# uNav44_r1_1.net
KiCad netlist of a schematic drawn in EAGLE
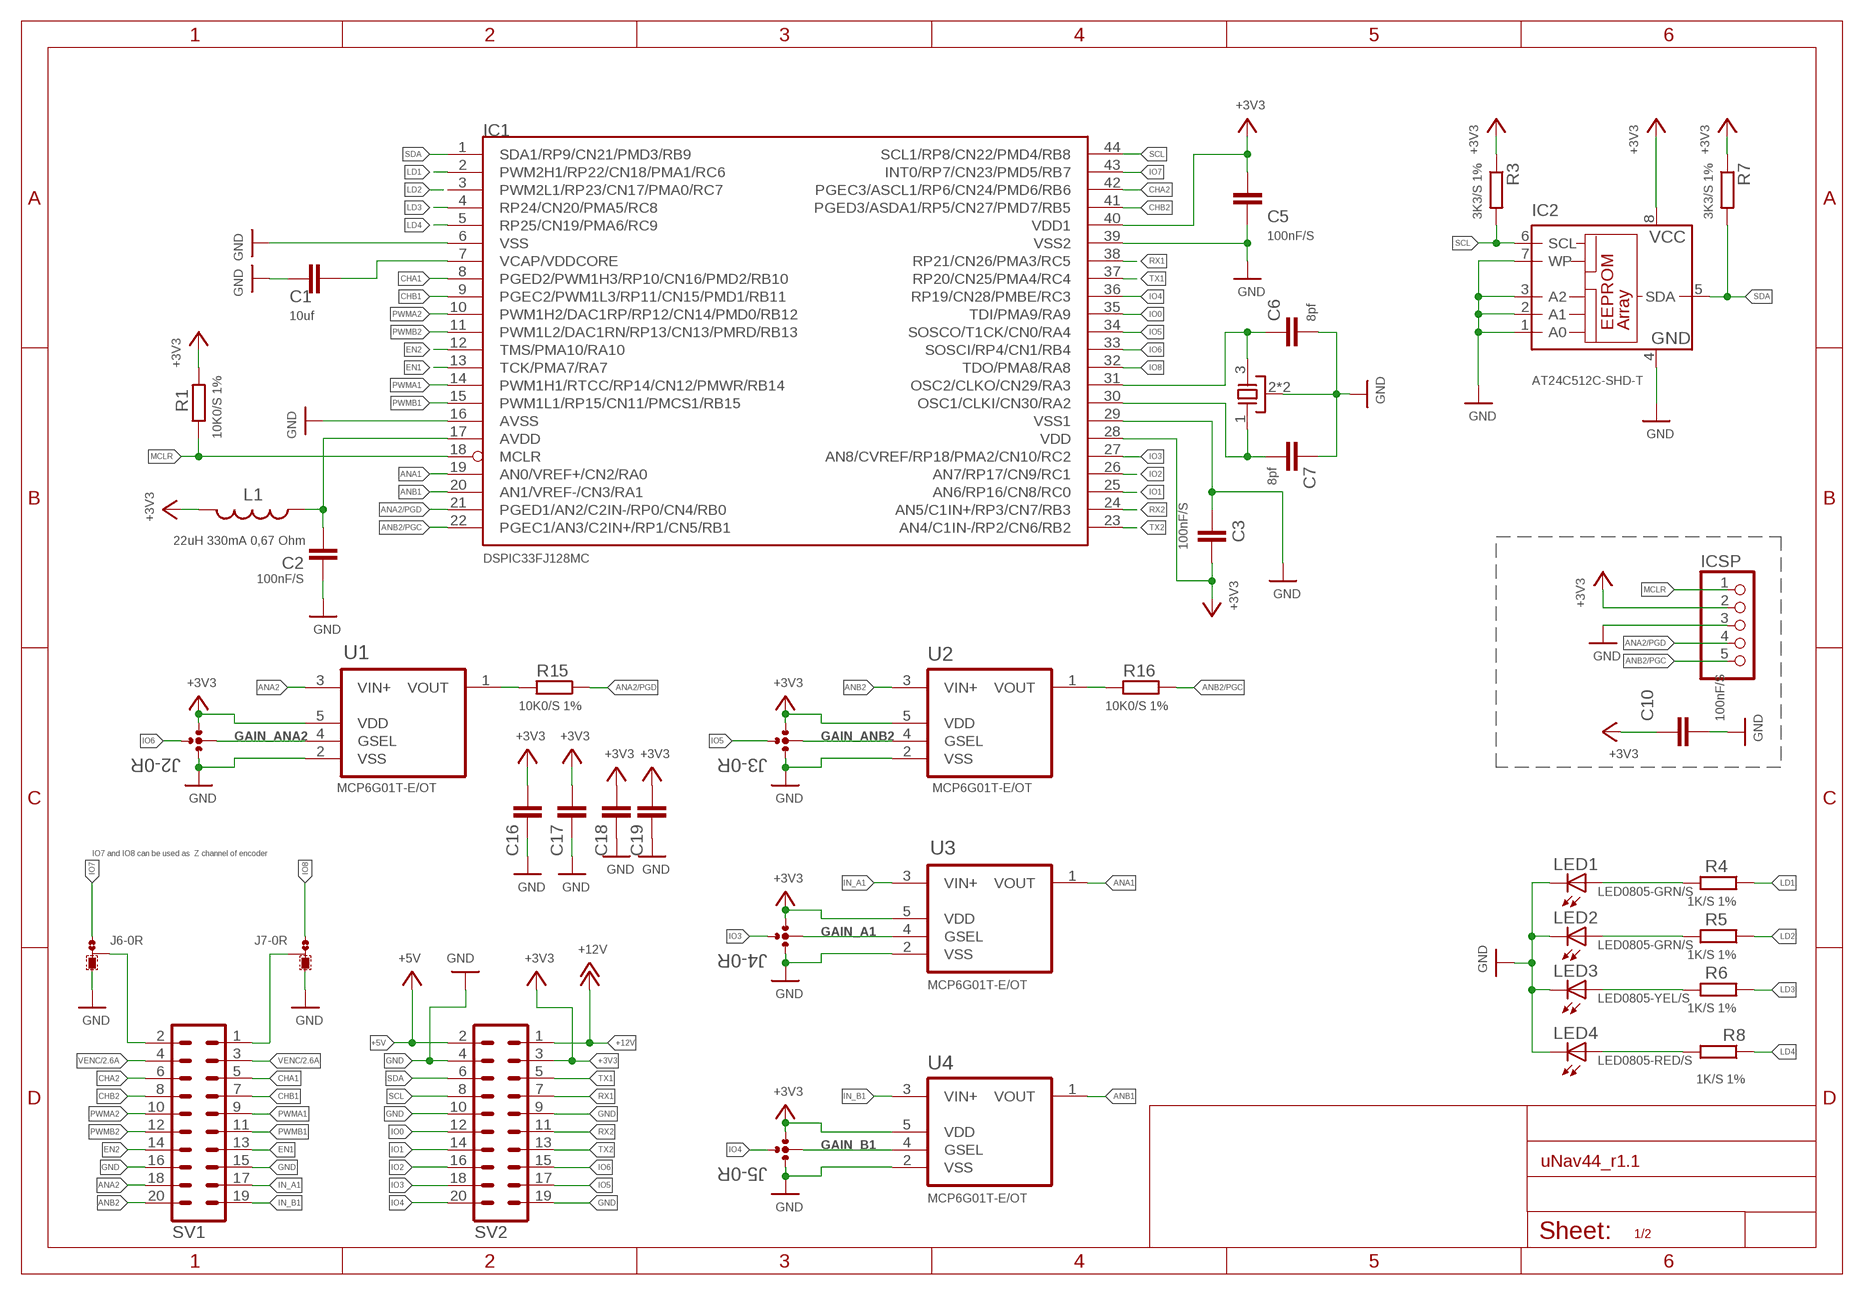
[diagram p0: schematic, sheet 1]
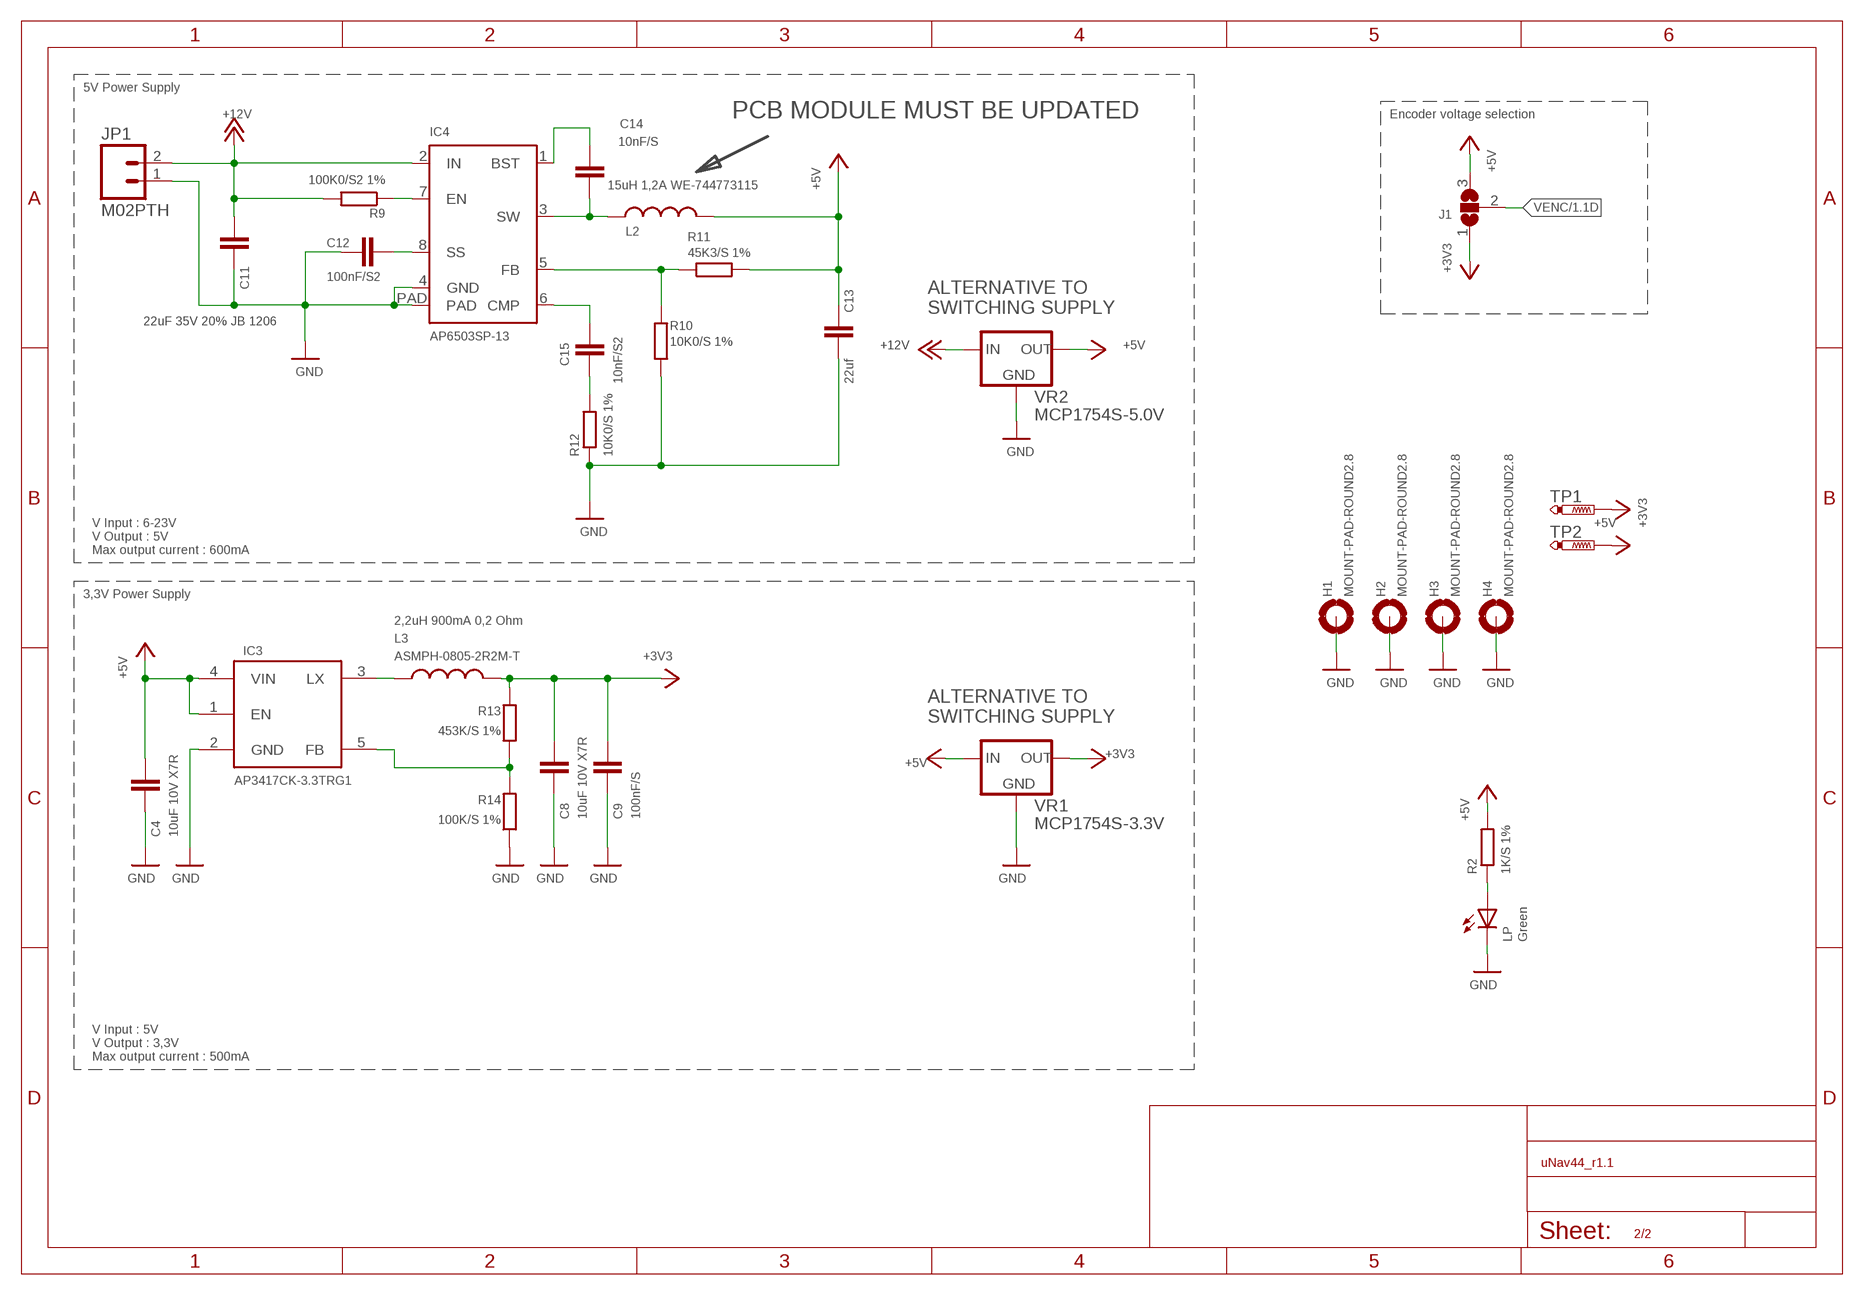
[diagram p1: schematic, sheet 2]

(export (version "E")
  (design (tool "Eeschema 10.0.6"))
  (components
    (comp (ref "C4")
      (value "10uF 10V X7R")
      (footprint "eagle-import:C0805")
      (libsource (lib "eagle-import") (part "C-EUC0805"))
    )
    (comp (ref "C8")
      (value "10uF 10V X7R")
      (footprint "eagle-import:C0805")
      (libsource (lib "eagle-import") (part "C-EUC0805"))
    )
    (comp (ref "C9")
      (value "100nF/S")
      (footprint "eagle-import:C0603")
      (libsource (lib "eagle-import") (part "C-EUC0603"))
    )
    (comp (ref "C11")
      (value "22uF 35V 20% JB 1206")
      (footprint "eagle-import:C1206")
      (libsource (lib "eagle-import") (part "C-EUC1206"))
    )
    (comp (ref "C12")
      (value "100nF/S2")
      (footprint "eagle-import:C0603")
      (libsource (lib "eagle-import") (part "C-EUC0603"))
    )
    (comp (ref "C13")
      (value "22uf")
      (footprint "eagle-import:C1206")
      (libsource (lib "eagle-import") (part "C-EUC1206"))
    )
    (comp (ref "C14")
      (value "10nF/S")
      (footprint "eagle-import:C0603")
      (libsource (lib "eagle-import") (part "C-EUC0603"))
    )
    (comp (ref "C15")
      (value "10nF/S2")
      (footprint "eagle-import:C0603")
      (libsource (lib "eagle-import") (part "C-EUC0603"))
    )
    (comp (ref "H1")
      (value "MOUNT-PAD-ROUND2.8")
      (footprint "eagle-import:2,8-PAD")
      (libsource (lib "eagle-import") (part "MOUNT-PAD-ROUND2.8"))
    )
    (comp (ref "H2")
      (value "MOUNT-PAD-ROUND2.8")
      (footprint "eagle-import:2,8-PAD")
      (libsource (lib "eagle-import") (part "MOUNT-PAD-ROUND2.8"))
    )
    (comp (ref "H3")
      (value "MOUNT-PAD-ROUND2.8")
      (footprint "eagle-import:2,8-PAD")
      (libsource (lib "eagle-import") (part "MOUNT-PAD-ROUND2.8"))
    )
    (comp (ref "H4")
      (value "MOUNT-PAD-ROUND2.8")
      (footprint "eagle-import:2,8-PAD")
      (libsource (lib "eagle-import") (part "MOUNT-PAD-ROUND2.8"))
    )
    (comp (ref "IC3")
      (value "AP3417CK-3.3TRG1")
      (footprint "eagle-import:SOT-23-5")
      (libsource (lib "eagle-import") (part "AP3417CSOT-23-5"))
    )
    (comp (ref "IC4")
      (value "AP6503SP-13")
      (footprint "eagle-import:SO-8EP")
      (libsource (lib "eagle-import") (part "AP6503SP-13'SO-8EP'"))
    )
    (comp (ref "J1")
      (value "SJ2W")
      (footprint "eagle-import:SJ_2")
      (libsource (lib "eagle-import") (part "SJ2W"))
    )
    (comp (ref "JP1")
      (value "M02PTH")
      (footprint "eagle-import:1X02")
      (libsource (lib "eagle-import") (part "M02PTH"))
    )
    (comp (ref "L2")
      (value "15uH 1,2A WE-744773115")
      (footprint "eagle-import:1210")
      (libsource (lib "eagle-import") (part "INDUCTOR1210"))
    )
    (comp (ref "L3")
      (value "ASMPH-0805-2R2M-T")
      (footprint "eagle-import:0805")
      (libsource (lib "eagle-import") (part "INDUCTOR0805"))
    )
    (comp (ref "LP")
      (value "Green")
      (footprint "eagle-import:CHIPLED_0805")
      (libsource (lib "eagle-import") (part "LEDCHIPLED_0805"))
    )
    (comp (ref "R2")
      (value "1K/S 1%")
      (footprint "eagle-import:R0603")
      (libsource (lib "eagle-import") (part "R-EU_R0603"))
    )
    (comp (ref "R9")
      (value "100K0/S2 1%")
      (footprint "eagle-import:R0603")
      (libsource (lib "eagle-import") (part "R-EU_R0603"))
    )
    (comp (ref "R10")
      (value "10K0/S 1%")
      (footprint "eagle-import:R0603")
      (libsource (lib "eagle-import") (part "R-EU_R0603"))
    )
    (comp (ref "R11")
      (value "45K3/S 1%")
      (footprint "eagle-import:R0603")
      (libsource (lib "eagle-import") (part "R-EU_R0603"))
    )
    (comp (ref "R12")
      (value "10K0/S 1%")
      (footprint "eagle-import:R0603")
      (libsource (lib "eagle-import") (part "R-EU_R0603"))
    )
    (comp (ref "R13")
      (value "453K/S 1%")
      (footprint "eagle-import:R0603")
      (libsource (lib "eagle-import") (part "R-EU_R0603"))
    )
    (comp (ref "R14")
      (value "100K/S 1%")
      (footprint "eagle-import:R0603")
      (libsource (lib "eagle-import") (part "R-EU_R0603"))
    )
    (comp (ref "TP1")
      (value "PTR1TP07R")
      (footprint "eagle-import:TP07R")
      (libsource (lib "eagle-import") (part "PTR1TP07R"))
    )
    (comp (ref "TP2")
      (value "PTR1TP07R")
      (footprint "eagle-import:TP07R")
      (libsource (lib "eagle-import") (part "PTR1TP07R"))
    )
    (comp (ref "VR1")
      (value "MCP1754S-3.3V")
      (footprint "eagle-import:SOT89")
      (libsource (lib "eagle-import") (part "MCP1754S"))
    )
    (comp (ref "VR2")
      (value "MCP1754S-5.0V")
      (footprint "eagle-import:SOT89")
      (libsource (lib "eagle-import") (part "MCP1754S"))
    )
    (comp (ref "C1")
      (value "10uf")
      (footprint "eagle-import:C1206")
      (libsource (lib "eagle-import") (part "C-EUC1206"))
    )
    (comp (ref "C2")
      (value "100nF/S")
      (footprint "eagle-import:C0603")
      (libsource (lib "eagle-import") (part "C-EUC0603"))
    )
    (comp (ref "C3")
      (value "100nF/S")
      (footprint "eagle-import:C0603")
      (libsource (lib "eagle-import") (part "C-EUC0603"))
    )
    (comp (ref "C5")
      (value "100nF/S")
      (footprint "eagle-import:C0603")
      (libsource (lib "eagle-import") (part "C-EUC0603"))
    )
    (comp (ref "C6")
      (value "8pf")
      (footprint "eagle-import:C0603")
      (libsource (lib "eagle-import") (part "C-EUC0603"))
    )
    (comp (ref "C7")
      (value "8pf")
      (footprint "eagle-import:C0603")
      (libsource (lib "eagle-import") (part "C-EUC0603"))
    )
    (comp (ref "C10")
      (value "100nF/S")
      (footprint "eagle-import:C0603")
      (libsource (lib "eagle-import") (part "C-EUC0603"))
    )
    (comp (ref "C16")
      (value "100nF/S")
      (footprint "eagle-import:C0603")
      (libsource (lib "eagle-import") (part "C-EUC0603"))
    )
    (comp (ref "C17")
      (value "100nF/S")
      (footprint "eagle-import:C0603")
      (libsource (lib "eagle-import") (part "C-EUC0603"))
    )
    (comp (ref "C18")
      (value "100nF/S")
      (footprint "eagle-import:C0603")
      (libsource (lib "eagle-import") (part "C-EUC0603"))
    )
    (comp (ref "C19")
      (value "100nF/S")
      (footprint "eagle-import:C0603")
      (libsource (lib "eagle-import") (part "C-EUC0603"))
    )
    (comp (ref "IC1")
      (value "DSPIC33FJ128MC")
      (footprint "eagle-import:TQFP44")
      (libsource (lib "eagle-import") (part "DSPIC33FJ128MC804-PT"))
    )
    (comp (ref "IC2")
      (value "AT24C512C-SHD-T")
      (footprint "eagle-import:SO-08M")
      (libsource (lib "eagle-import") (part "24SMAA01"))
    )
    (comp (ref "ICSP")
      (value "PINHD-1X05_2.54-S")
      (footprint "eagle-import:1X05-S")
      (libsource (lib "eagle-import") (part "PINHD-1X05_2.54-S"))
    )
    (comp (ref "J2")
      (value "0R-JUMP-4")
      (footprint "eagle-import:C0R-JUMP-4")
      (libsource (lib "eagle-import") (part "0R-JUMP-4"))
    )
    (comp (ref "J3")
      (value "0R-JUMP-4")
      (footprint "eagle-import:C0R-JUMP-4")
      (libsource (lib "eagle-import") (part "0R-JUMP-4"))
    )
    (comp (ref "J4")
      (value "0R-JUMP-4")
      (footprint "eagle-import:C0R-JUMP-4")
      (libsource (lib "eagle-import") (part "0R-JUMP-4"))
    )
    (comp (ref "J5")
      (value "0R-JUMP-4")
      (footprint "eagle-import:C0R-JUMP-4")
      (libsource (lib "eagle-import") (part "0R-JUMP-4"))
    )
    (comp (ref "J6")
      (value "0R-JUMPC")
      (footprint "eagle-import:C0R-JMP")
      (libsource (lib "eagle-import") (part "0R-JUMPC"))
    )
    (comp (ref "J7")
      (value "0R-JUMPC")
      (footprint "eagle-import:C0R-JMP")
      (libsource (lib "eagle-import") (part "0R-JUMPC"))
    )
    (comp (ref "L1")
      (value "22uH 330mA 0,67 Ohm")
      (footprint "eagle-import:0805")
      (libsource (lib "eagle-import") (part "INDUCTOR0805"))
    )
    (comp (ref "LED1")
      (value "LED0805-GRN/S")
      (footprint "eagle-import:CHIPLED_0805")
      (libsource (lib "eagle-import") (part "LEDCHIPLED_0805"))
    )
    (comp (ref "LED2")
      (value "LED0805-GRN/S")
      (footprint "eagle-import:CHIPLED_0805")
      (libsource (lib "eagle-import") (part "LEDCHIPLED_0805"))
    )
    (comp (ref "LED3")
      (value "LED0805-YEL/S")
      (footprint "eagle-import:CHIPLED_0805")
      (libsource (lib "eagle-import") (part "LEDCHIPLED_0805"))
    )
    (comp (ref "LED4")
      (value "LED0805-RED/S")
      (footprint "eagle-import:CHIPLED_0805")
      (libsource (lib "eagle-import") (part "LEDCHIPLED_0805"))
    )
    (comp (ref "R1")
      (value "10K0/S 1%")
      (footprint "eagle-import:R0603")
      (libsource (lib "eagle-import") (part "R-EU_R0603"))
    )
    (comp (ref "R3")
      (value "3K3/S 1%")
      (footprint "eagle-import:R0603")
      (libsource (lib "eagle-import") (part "R-EU_R0603"))
    )
    (comp (ref "R4")
      (value "1K/S 1%")
      (footprint "eagle-import:R0603")
      (libsource (lib "eagle-import") (part "R-EU_R0603"))
    )
    (comp (ref "R5")
      (value "1K/S 1%")
      (footprint "eagle-import:R0603")
      (libsource (lib "eagle-import") (part "R-EU_R0603"))
    )
    (comp (ref "R6")
      (value "1K/S 1%")
      (footprint "eagle-import:R0603")
      (libsource (lib "eagle-import") (part "R-EU_R0603"))
    )
    (comp (ref "R7")
      (value "3K3/S 1%")
      (footprint "eagle-import:R0603")
      (libsource (lib "eagle-import") (part "R-EU_R0603"))
    )
    (comp (ref "R8")
      (value "1K/S 1%")
      (footprint "eagle-import:R0603")
      (libsource (lib "eagle-import") (part "R-EU_R0603"))
    )
    (comp (ref "R15")
      (value "10K0/S 1%")
      (footprint "eagle-import:R0603")
      (libsource (lib "eagle-import") (part "R-EU_R0603"))
    )
    (comp (ref "R16")
      (value "10K0/S 1%")
      (footprint "eagle-import:R0603")
      (libsource (lib "eagle-import") (part "R-EU_R0603"))
    )
    (comp (ref "SV1")
      (value "MA10-2")
      (footprint "eagle-import:MA10-2")
      (fields (field (name "OC_FARNELL") "unknown") (field (name "OC_NEWARK") "unknown"))
      (libsource (lib "eagle-import") (part "MA10-2"))
    )
    (comp (ref "SV2")
      (value "MA10-2")
      (footprint "eagle-import:MA10-2")
      (libsource (lib "eagle-import") (part "MA10-2"))
    )
    (comp (ref "U1")
      (value "MCP6G01T-E/OT")
      (footprint "eagle-import:SOT95P300X145-5N")
      (libsource (lib "eagle-import") (part "MCP6G01T-E/OT"))
    )
    (comp (ref "U2")
      (value "MCP6G01T-E/OT")
      (footprint "eagle-import:SOT95P300X145-5N")
      (libsource (lib "eagle-import") (part "MCP6G01T-E/OT"))
    )
    (comp (ref "U3")
      (value "MCP6G01T-E/OT")
      (footprint "eagle-import:SOT95P300X145-5N")
      (libsource (lib "eagle-import") (part "MCP6G01T-E/OT"))
    )
    (comp (ref "U4")
      (value "MCP6G01T-E/OT")
      (footprint "eagle-import:SOT95P300X145-5N")
      (libsource (lib "eagle-import") (part "MCP6G01T-E/OT"))
    )
    (comp (ref "XT1")
      (value "CTS_32X25_SMD")
      (footprint "eagle-import:CTS_32X25")
      (libsource (lib "eagle-import") (part "CTS_32X25_SMD"))
    )
  )
  (nets
    (net (code "1") (name "+3V3") (class "Default")
      (node (ref "C10") (pin "1") (pinfunction "1_1") (pintype "passive"))
      (node (ref "C16") (pin "1") (pinfunction "1_1") (pintype "passive"))
      (node (ref "C17") (pin "1") (pinfunction "1_1") (pintype "passive"))
      (node (ref "C18") (pin "1") (pinfunction "1_1") (pintype "passive"))
      (node (ref "C19") (pin "1") (pinfunction "1_1") (pintype "passive"))
      (node (ref "C3") (pin "1") (pinfunction "1_1") (pintype "passive"))
      (node (ref "C5") (pin "2") (pinfunction "2_2") (pintype "passive"))
      (node (ref "C8") (pin "1") (pinfunction "1_1") (pintype "passive"))
      (node (ref "C9") (pin "1") (pinfunction "1_1") (pintype "passive"))
      (node (ref "IC1") (pin "28") (pinfunction "VDD_28") (pintype "power_in"))
      (node (ref "IC1") (pin "40") (pinfunction "VDD1_40") (pintype "power_in"))
      (node (ref "IC2") (pin "8") (pinfunction "VCC_8") (pintype "power_in"))
      (node (ref "ICSP") (pin "2") (pinfunction "2_2") (pintype "passive"))
      (node (ref "J1") (pin "1") (pinfunction "1_1") (pintype "passive"))
      (node (ref "J2") (pin "1") (pinfunction "1_1") (pintype "passive"))
      (node (ref "J3") (pin "1") (pinfunction "1_1") (pintype "passive"))
      (node (ref "J4") (pin "1") (pinfunction "1_1") (pintype "passive"))
      (node (ref "J5") (pin "1") (pinfunction "1_1") (pintype "passive"))
      (node (ref "L1") (pin "2") (pinfunction "2_2") (pintype "passive"))
      (node (ref "L3") (pin "2") (pinfunction "2_2") (pintype "passive"))
      (node (ref "R1") (pin "2") (pinfunction "2_2") (pintype "passive"))
      (node (ref "R13") (pin "2") (pinfunction "2_2") (pintype "passive"))
      (node (ref "R3") (pin "1") (pinfunction "1_1") (pintype "passive"))
      (node (ref "R7") (pin "1") (pinfunction "1_1") (pintype "passive"))
      (node (ref "SV2") (pin "3") (pinfunction "3_3") (pintype "passive"))
      (node (ref "TP1") (pin "TP") (pinfunction "TP_TP") (pintype "input"))
      (node (ref "U1") (pin "5") (pinfunction "VDD_5") (pintype "power_in"))
      (node (ref "U2") (pin "5") (pinfunction "VDD_5") (pintype "power_in"))
      (node (ref "U3") (pin "5") (pinfunction "VDD_5") (pintype "power_in"))
      (node (ref "U4") (pin "5") (pinfunction "VDD_5") (pintype "power_in"))
      (node (ref "VR1") (pin "3") (pinfunction "OUT_3") (pintype "passive"))
    )
    (net (code "2") (name "+5V") (class "Default")
      (node (ref "C13") (pin "1") (pinfunction "1_1") (pintype "passive"))
      (node (ref "C4") (pin "1") (pinfunction "1_1") (pintype "passive"))
      (node (ref "IC3") (pin "1") (pinfunction "EN_1") (pintype "bidirectional"))
      (node (ref "IC3") (pin "4") (pinfunction "VIN_4") (pintype "bidirectional"))
      (node (ref "J1") (pin "3") (pinfunction "3_3") (pintype "passive"))
      (node (ref "L2") (pin "2") (pinfunction "2_2") (pintype "passive"))
      (node (ref "R11") (pin "2") (pinfunction "2_2") (pintype "passive"))
      (node (ref "R2") (pin "2") (pinfunction "2_2") (pintype "passive"))
      (node (ref "SV2") (pin "2") (pinfunction "2_2") (pintype "passive"))
      (node (ref "TP2") (pin "TP") (pinfunction "TP_TP") (pintype "input"))
      (node (ref "VR1") (pin "1") (pinfunction "IN_1") (pintype "input"))
      (node (ref "VR2") (pin "3") (pinfunction "OUT_3") (pintype "passive"))
    )
    (net (code "3") (name "+12V") (class "Default")
      (node (ref "C11") (pin "1") (pinfunction "1_1") (pintype "passive"))
      (node (ref "IC4") (pin "2") (pinfunction "IN_2") (pintype "power_in"))
      (node (ref "JP1") (pin "2") (pinfunction "2_2") (pintype "passive"))
      (node (ref "R9") (pin "2") (pinfunction "2_2") (pintype "passive"))
      (node (ref "SV2") (pin "1") (pinfunction "1_1") (pintype "passive"))
      (node (ref "VR2") (pin "1") (pinfunction "IN_1") (pintype "input"))
    )
    (net (code "4") (name "ANA1") (class "Default")
      (node (ref "IC1") (pin "19") (pinfunction "AN0/VREF+/CN2/RA0_19") (pintype "bidirectional"))
      (node (ref "U3") (pin "1") (pinfunction "VOUT_1") (pintype "output"))
    )
    (net (code "5") (name "ANA2") (class "Default")
      (node (ref "SV1") (pin "18") (pinfunction "18_18") (pintype "passive"))
      (node (ref "U1") (pin "3") (pinfunction "VIN+_3") (pintype "input"))
    )
    (net (code "6") (name "ANA2{slash}PGD") (class "Default")
      (node (ref "IC1") (pin "21") (pinfunction "PGED1/AN2/C2IN-/RP0/CN4/RB0_21") (pintype "bidirectional"))
      (node (ref "ICSP") (pin "4") (pinfunction "4_4") (pintype "passive"))
      (node (ref "R15") (pin "1") (pinfunction "1_1") (pintype "passive"))
    )
    (net (code "7") (name "ANB1") (class "Default")
      (node (ref "IC1") (pin "20") (pinfunction "AN1/VREF-/CN3/RA1_20") (pintype "bidirectional"))
      (node (ref "U4") (pin "1") (pinfunction "VOUT_1") (pintype "output"))
    )
    (net (code "8") (name "ANB2") (class "Default")
      (node (ref "SV1") (pin "20") (pinfunction "20_20") (pintype "passive"))
      (node (ref "U2") (pin "3") (pinfunction "VIN+_3") (pintype "input"))
    )
    (net (code "9") (name "ANB2{slash}PGC") (class "Default")
      (node (ref "IC1") (pin "22") (pinfunction "PGEC1/AN3/C2IN+/RP1/CN5/RB1_22") (pintype "bidirectional"))
      (node (ref "ICSP") (pin "5") (pinfunction "5_5") (pintype "passive"))
      (node (ref "R16") (pin "1") (pinfunction "1_1") (pintype "passive"))
    )
    (net (code "10") (name "CHA1") (class "Default")
      (node (ref "IC1") (pin "8") (pinfunction "PGED2/PWM1H3/RP10/CN16/PMD2/RB10_8") (pintype "bidirectional"))
      (node (ref "SV1") (pin "5") (pinfunction "5_5") (pintype "passive"))
    )
    (net (code "11") (name "CHA2") (class "Default")
      (node (ref "IC1") (pin "42") (pinfunction "PGEC3/ASCL1/RP6/CN24/PMD6/RB6_42") (pintype "bidirectional"))
      (node (ref "SV1") (pin "6") (pinfunction "6_6") (pintype "passive"))
    )
    (net (code "12") (name "CHB1") (class "Default")
      (node (ref "IC1") (pin "9") (pinfunction "PGEC2/PWM1L3/RP11/CN15/PMD1/RB11_9") (pintype "bidirectional"))
      (node (ref "SV1") (pin "7") (pinfunction "7_7") (pintype "passive"))
    )
    (net (code "13") (name "CHB2") (class "Default")
      (node (ref "IC1") (pin "41") (pinfunction "PGED3/ASDA1/RP5/CN27/PMD7/RB5_41") (pintype "bidirectional"))
      (node (ref "SV1") (pin "8") (pinfunction "8_8") (pintype "passive"))
    )
    (net (code "14") (name "EN1") (class "Default")
      (node (ref "IC1") (pin "13") (pinfunction "TCK/PMA7/RA7_13") (pintype "bidirectional"))
      (node (ref "SV1") (pin "13") (pinfunction "13_13") (pintype "passive"))
    )
    (net (code "15") (name "EN2") (class "Default")
      (node (ref "IC1") (pin "12") (pinfunction "TMS/PMA10/RA10_12") (pintype "bidirectional"))
      (node (ref "SV1") (pin "14") (pinfunction "14_14") (pintype "passive"))
    )
    (net (code "16") (name "GAIN_A1") (class "Default")
      (node (ref "J4") (pin "2") (pinfunction "2_2") (pintype "passive"))
      (node (ref "U3") (pin "4") (pinfunction "GSEL_4") (pintype "input"))
    )
    (net (code "17") (name "GAIN_ANA2") (class "Default")
      (node (ref "J2") (pin "2") (pinfunction "2_2") (pintype "passive"))
      (node (ref "U1") (pin "4") (pinfunction "GSEL_4") (pintype "input"))
    )
    (net (code "18") (name "GAIN_ANB2") (class "Default")
      (node (ref "J3") (pin "2") (pinfunction "2_2") (pintype "passive"))
      (node (ref "U2") (pin "4") (pinfunction "GSEL_4") (pintype "input"))
    )
    (net (code "19") (name "GAIN_B1") (class "Default")
      (node (ref "J5") (pin "2") (pinfunction "2_2") (pintype "passive"))
      (node (ref "U4") (pin "4") (pinfunction "GSEL_4") (pintype "input"))
    )
    (net (code "20") (name "GND") (class "Default")
      (node (ref "C1") (pin "2") (pinfunction "2_2") (pintype "passive"))
      (node (ref "C10") (pin "2") (pinfunction "2_2") (pintype "passive"))
      (node (ref "C11") (pin "2") (pinfunction "2_2") (pintype "passive"))
      (node (ref "C12") (pin "2") (pinfunction "2_2") (pintype "passive"))
      (node (ref "C13") (pin "2") (pinfunction "2_2") (pintype "passive"))
      (node (ref "C16") (pin "2") (pinfunction "2_2") (pintype "passive"))
      (node (ref "C17") (pin "2") (pinfunction "2_2") (pintype "passive"))
      (node (ref "C18") (pin "2") (pinfunction "2_2") (pintype "passive"))
      (node (ref "C19") (pin "2") (pinfunction "2_2") (pintype "passive"))
      (node (ref "C2") (pin "1") (pinfunction "1_1") (pintype "passive"))
      (node (ref "C3") (pin "2") (pinfunction "2_2") (pintype "passive"))
      (node (ref "C4") (pin "2") (pinfunction "2_2") (pintype "passive"))
      (node (ref "C5") (pin "1") (pinfunction "1_1") (pintype "passive"))
      (node (ref "C6") (pin "2") (pinfunction "2_2") (pintype "passive"))
      (node (ref "C7") (pin "1") (pinfunction "1_1") (pintype "passive"))
      (node (ref "C8") (pin "2") (pinfunction "2_2") (pintype "passive"))
      (node (ref "C9") (pin "2") (pinfunction "2_2") (pintype "passive"))
      (node (ref "H1") (pin "B2,8") (pinfunction "MOUNT_B2,8") (pintype "passive"))
      (node (ref "H2") (pin "B2,8") (pinfunction "MOUNT_B2,8") (pintype "passive"))
      (node (ref "H3") (pin "B2,8") (pinfunction "MOUNT_B2,8") (pintype "passive"))
      (node (ref "H4") (pin "B2,8") (pinfunction "MOUNT_B2,8") (pintype "passive"))
      (node (ref "IC1") (pin "16") (pinfunction "AVSS_16") (pintype "power_in"))
      (node (ref "IC1") (pin "29") (pinfunction "VSS1_29") (pintype "power_in"))
      (node (ref "IC1") (pin "39") (pinfunction "VSS2_39") (pintype "power_in"))
      (node (ref "IC1") (pin "6") (pinfunction "VSS_6") (pintype "power_in"))
      (node (ref "IC2") (pin "1") (pinfunction "A0_1") (pintype "input"))
      (node (ref "IC2") (pin "2") (pinfunction "A1_2") (pintype "input"))
      (node (ref "IC2") (pin "3") (pinfunction "A2_3") (pintype "input"))
      (node (ref "IC2") (pin "4") (pinfunction "GND_4") (pintype "power_in"))
      (node (ref "IC2") (pin "7") (pinfunction "WP_7") (pintype "input"))
      (node (ref "IC3") (pin "2") (pinfunction "GND_2") (pintype "bidirectional"))
      (node (ref "IC4") (pin "4") (pinfunction "GND_4") (pintype "power_in"))
      (node (ref "IC4") (pin "PAD") (pinfunction "PAD_PAD") (pintype "power_in"))
      (node (ref "ICSP") (pin "3") (pinfunction "3_3") (pintype "passive"))
      (node (ref "J2") (pin "3") (pinfunction "3_3") (pintype "passive"))
      (node (ref "J3") (pin "3") (pinfunction "3_3") (pintype "passive"))
      (node (ref "J4") (pin "3") (pinfunction "3_3") (pintype "passive"))
      (node (ref "J5") (pin "3") (pinfunction "3_3") (pintype "passive"))
      (node (ref "J6") (pin "3") (pinfunction "3_3") (pintype "passive"))
      (node (ref "J7") (pin "3") (pinfunction "3_3") (pintype "passive"))
      (node (ref "JP1") (pin "1") (pinfunction "1_1") (pintype "passive"))
      (node (ref "LED1") (pin "C") (pinfunction "C_C") (pintype "passive"))
      (node (ref "LED2") (pin "C") (pinfunction "C_C") (pintype "passive"))
      (node (ref "LED3") (pin "C") (pinfunction "C_C") (pintype "passive"))
      (node (ref "LED4") (pin "C") (pinfunction "C_C") (pintype "passive"))
      (node (ref "LP") (pin "C") (pinfunction "C_C") (pintype "passive"))
      (node (ref "R10") (pin "2") (pinfunction "2_2") (pintype "passive"))
      (node (ref "R12") (pin "1") (pinfunction "1_1") (pintype "passive"))
      (node (ref "R14") (pin "1") (pinfunction "1_1") (pintype "passive"))
      (node (ref "SV1") (pin "15") (pinfunction "15_15") (pintype "passive"))
      (node (ref "SV1") (pin "16") (pinfunction "16_16") (pintype "passive"))
      (node (ref "SV2") (pin "10") (pinfunction "10_10") (pintype "passive"))
      (node (ref "SV2") (pin "19") (pinfunction "19_19") (pintype "passive"))
      (node (ref "SV2") (pin "4") (pinfunction "4_4") (pintype "passive"))
      (node (ref "SV2") (pin "9") (pinfunction "9_9") (pintype "passive"))
      (node (ref "U1") (pin "2") (pinfunction "VSS_2") (pintype "passive"))
      (node (ref "U2") (pin "2") (pinfunction "VSS_2") (pintype "passive"))
      (node (ref "U3") (pin "2") (pinfunction "VSS_2") (pintype "passive"))
      (node (ref "U4") (pin "2") (pinfunction "VSS_2") (pintype "passive"))
      (node (ref "VR1") (pin "2") (pinfunction "GND_2") (pintype "input"))
      (node (ref "VR1") (pin "4") (pinfunction "GND_4") (pintype "input"))
      (node (ref "VR2") (pin "2") (pinfunction "GND_2") (pintype "input"))
      (node (ref "VR2") (pin "4") (pinfunction "GND_4") (pintype "input"))
      (node (ref "XT1") (pin "2") (pinfunction "GND_2") (pintype "power_in"))
      (node (ref "XT1") (pin "4") (pinfunction "GND_4") (pintype "power_in"))
    )
    (net (code "21") (name "IN_A1") (class "Default")
      (node (ref "SV1") (pin "17") (pinfunction "17_17") (pintype "passive"))
      (node (ref "U3") (pin "3") (pinfunction "VIN+_3") (pintype "input"))
    )
    (net (code "22") (name "IN_B1") (class "Default")
      (node (ref "SV1") (pin "19") (pinfunction "19_19") (pintype "passive"))
      (node (ref "U4") (pin "3") (pinfunction "VIN+_3") (pintype "input"))
    )
    (net (code "23") (name "IO0") (class "Default")
      (node (ref "IC1") (pin "35") (pinfunction "TDI/PMA9/RA9_35") (pintype "bidirectional"))
      (node (ref "SV2") (pin "12") (pinfunction "12_12") (pintype "passive"))
    )
    (net (code "24") (name "IO1") (class "Default")
      (node (ref "IC1") (pin "25") (pinfunction "AN6/RP16/CN8/RC0_25") (pintype "bidirectional"))
      (node (ref "SV2") (pin "14") (pinfunction "14_14") (pintype "passive"))
    )
    (net (code "25") (name "IO2") (class "Default")
      (node (ref "IC1") (pin "26") (pinfunction "AN7/RP17/CN9/RC1_26") (pintype "bidirectional"))
      (node (ref "SV2") (pin "16") (pinfunction "16_16") (pintype "passive"))
    )
    (net (code "26") (name "IO3") (class "Default")
      (node (ref "IC1") (pin "27") (pinfunction "AN8/CVREF/RP18/PMA2/CN10/RC2_27") (pintype "bidirectional"))
      (node (ref "J4") (pin "4") (pinfunction "4_4") (pintype "passive"))
      (node (ref "SV2") (pin "18") (pinfunction "18_18") (pintype "passive"))
    )
    (net (code "27") (name "IO4") (class "Default")
      (node (ref "IC1") (pin "36") (pinfunction "RP19/CN28/PMBE/RC3_36") (pintype "bidirectional"))
      (node (ref "J5") (pin "4") (pinfunction "4_4") (pintype "passive"))
      (node (ref "SV2") (pin "20") (pinfunction "20_20") (pintype "passive"))
    )
    (net (code "28") (name "IO5") (class "Default")
      (node (ref "IC1") (pin "34") (pinfunction "SOSCO/T1CK/CN0/RA4_34") (pintype "bidirectional"))
      (node (ref "J3") (pin "4") (pinfunction "4_4") (pintype "passive"))
      (node (ref "SV2") (pin "17") (pinfunction "17_17") (pintype "passive"))
    )
    (net (code "29") (name "IO6") (class "Default")
      (node (ref "IC1") (pin "33") (pinfunction "SOSCI/RP4/CN1/RB4_33") (pintype "bidirectional"))
      (node (ref "J2") (pin "4") (pinfunction "4_4") (pintype "passive"))
      (node (ref "SV2") (pin "15") (pinfunction "15_15") (pintype "passive"))
    )
    (net (code "30") (name "IO7") (class "Default")
      (node (ref "IC1") (pin "43") (pinfunction "INT0/RP7/CN23/PMD5/RB7_43") (pintype "bidirectional"))
      (node (ref "J6") (pin "1") (pinfunction "1_1") (pintype "passive"))
    )
    (net (code "31") (name "IO8") (class "Default")
      (node (ref "IC1") (pin "32") (pinfunction "TDO/PMA8/RA8_32") (pintype "bidirectional"))
      (node (ref "J7") (pin "1") (pinfunction "1_1") (pintype "passive"))
    )
    (net (code "32") (name "LD1") (class "Default")
      (node (ref "IC1") (pin "2") (pinfunction "PWM2H1/RP22/CN18/PMA1/RC6_2") (pintype "bidirectional"))
      (node (ref "R4") (pin "1") (pinfunction "1_1") (pintype "passive"))
    )
    (net (code "33") (name "LD2") (class "Default")
      (node (ref "IC1") (pin "3") (pinfunction "PWM2L1/RP23/CN17/PMA0/RC7_3") (pintype "bidirectional"))
      (node (ref "R5") (pin "1") (pinfunction "1_1") (pintype "passive"))
    )
    (net (code "34") (name "LD3") (class "Default")
      (node (ref "IC1") (pin "4") (pinfunction "RP24/CN20/PMA5/RC8_4") (pintype "bidirectional"))
      (node (ref "R6") (pin "1") (pinfunction "1_1") (pintype "passive"))
    )
    (net (code "35") (name "LD4") (class "Default")
      (node (ref "IC1") (pin "5") (pinfunction "RP25/CN19/PMA6/RC9_5") (pintype "bidirectional"))
      (node (ref "R8") (pin "1") (pinfunction "1_1") (pintype "passive"))
    )
    (net (code "36") (name "MCLR") (class "Default")
      (node (ref "IC1") (pin "18") (pinfunction "MCLR_18") (pintype "input"))
      (node (ref "ICSP") (pin "1") (pinfunction "1_1") (pintype "passive"))
      (node (ref "R1") (pin "1") (pinfunction "1_1") (pintype "passive"))
    )
    (net (code "37") (name "Net-(C15-Pad2)") (class "Default")
      (node (ref "C15") (pin "2") (pinfunction "2_2") (pintype "passive"))
      (node (ref "R12") (pin "2") (pinfunction "2_2") (pintype "passive"))
    )
    (net (code "38") (name "Net-(IC1-AVDD)") (class "Default")
      (node (ref "C2") (pin "2") (pinfunction "2_2") (pintype "passive"))
      (node (ref "IC1") (pin "17") (pinfunction "AVDD_17") (pintype "power_in"))
      (node (ref "L1") (pin "1") (pinfunction "1_1") (pintype "passive"))
    )
    (net (code "39") (name "Net-(IC1-OSC1{slash}CLKI{slash}CN30{slash}RA2)") (class "Default")
      (node (ref "C7") (pin "2") (pinfunction "2_2") (pintype "passive"))
      (node (ref "IC1") (pin "30") (pinfunction "OSC1/CLKI/CN30/RA2_30") (pintype "bidirectional"))
      (node (ref "XT1") (pin "1") (pinfunction "X1_1") (pintype "bidirectional"))
    )
    (net (code "40") (name "Net-(IC1-OSC2{slash}CLKO{slash}CN29{slash}RA3)") (class "Default")
      (node (ref "C6") (pin "1") (pinfunction "1_1") (pintype "passive"))
      (node (ref "IC1") (pin "31") (pinfunction "OSC2/CLKO/CN29/RA3_31") (pintype "bidirectional"))
      (node (ref "XT1") (pin "3") (pinfunction "X2_3") (pintype "bidirectional"))
    )
    (net (code "41") (name "Net-(IC1-VCAP{slash}VDDCORE)") (class "Default")
      (node (ref "C1") (pin "1") (pinfunction "1_1") (pintype "passive"))
      (node (ref "IC1") (pin "7") (pinfunction "VCAP/VDDCORE_7") (pintype "power_in"))
    )
    (net (code "42") (name "Net-(IC3-FB)") (class "Default")
      (node (ref "IC3") (pin "5") (pinfunction "FB_5") (pintype "bidirectional"))
      (node (ref "R13") (pin "1") (pinfunction "1_1") (pintype "passive"))
      (node (ref "R14") (pin "2") (pinfunction "2_2") (pintype "passive"))
    )
    (net (code "43") (name "Net-(IC3-LX)") (class "Default")
      (node (ref "IC3") (pin "3") (pinfunction "LX_3") (pintype "bidirectional"))
      (node (ref "L3") (pin "1") (pinfunction "1_1") (pintype "passive"))
    )
    (net (code "44") (name "Net-(IC4-BST)") (class "Default")
      (node (ref "C14") (pin "1") (pinfunction "1_1") (pintype "passive"))
      (node (ref "IC4") (pin "1") (pinfunction "BST_1") (pintype "bidirectional"))
    )
    (net (code "45") (name "Net-(IC4-CMP)") (class "Default")
      (node (ref "C15") (pin "1") (pinfunction "1_1") (pintype "passive"))
      (node (ref "IC4") (pin "6") (pinfunction "CMP_6") (pintype "bidirectional"))
    )
    (net (code "46") (name "Net-(IC4-EN)") (class "Default")
      (node (ref "IC4") (pin "7") (pinfunction "EN_7") (pintype "bidirectional"))
      (node (ref "R9") (pin "1") (pinfunction "1_1") (pintype "passive"))
    )
    (net (code "47") (name "Net-(IC4-FB)") (class "Default")
      (node (ref "IC4") (pin "5") (pinfunction "FB_5") (pintype "bidirectional"))
      (node (ref "R10") (pin "1") (pinfunction "1_1") (pintype "passive"))
      (node (ref "R11") (pin "1") (pinfunction "1_1") (pintype "passive"))
    )
    (net (code "48") (name "Net-(IC4-SS)") (class "Default")
      (node (ref "C12") (pin "1") (pinfunction "1_1") (pintype "passive"))
      (node (ref "IC4") (pin "8") (pinfunction "SS_8") (pintype "bidirectional"))
    )
    (net (code "49") (name "Net-(IC4-SW)") (class "Default")
      (node (ref "C14") (pin "2") (pinfunction "2_2") (pintype "passive"))
      (node (ref "IC4") (pin "3") (pinfunction "SW_3") (pintype "bidirectional"))
      (node (ref "L2") (pin "1") (pinfunction "1_1") (pintype "passive"))
    )
    (net (code "50") (name "Net-(J6-Pad2)") (class "Default")
      (node (ref "J6") (pin "2") (pinfunction "2_2") (pintype "passive"))
      (node (ref "SV1") (pin "2") (pinfunction "2_2") (pintype "passive"))
    )
    (net (code "51") (name "Net-(J7-Pad2)") (class "Default")
      (node (ref "J7") (pin "2") (pinfunction "2_2") (pintype "passive"))
      (node (ref "SV1") (pin "1") (pinfunction "1_1") (pintype "passive"))
    )
    (net (code "52") (name "Net-(LED1-PadA)") (class "Default")
      (node (ref "LED1") (pin "A") (pinfunction "A_A") (pintype "passive"))
      (node (ref "R4") (pin "2") (pinfunction "2_2") (pintype "passive"))
    )
    (net (code "53") (name "Net-(LED2-PadA)") (class "Default")
      (node (ref "LED2") (pin "A") (pinfunction "A_A") (pintype "passive"))
      (node (ref "R5") (pin "2") (pinfunction "2_2") (pintype "passive"))
    )
    (net (code "54") (name "Net-(LED3-PadA)") (class "Default")
      (node (ref "LED3") (pin "A") (pinfunction "A_A") (pintype "passive"))
      (node (ref "R6") (pin "2") (pinfunction "2_2") (pintype "passive"))
    )
    (net (code "55") (name "Net-(LED4-PadA)") (class "Default")
      (node (ref "LED4") (pin "A") (pinfunction "A_A") (pintype "passive"))
      (node (ref "R8") (pin "2") (pinfunction "2_2") (pintype "passive"))
    )
    (net (code "56") (name "Net-(LP-PadA)") (class "Default")
      (node (ref "LP") (pin "A") (pinfunction "A_A") (pintype "passive"))
      (node (ref "R2") (pin "1") (pinfunction "1_1") (pintype "passive"))
    )
    (net (code "57") (name "Net-(U1-VOUT)") (class "Default")
      (node (ref "R15") (pin "2") (pinfunction "2_2") (pintype "passive"))
      (node (ref "U1") (pin "1") (pinfunction "VOUT_1") (pintype "output"))
    )
    (net (code "58") (name "Net-(U2-VOUT)") (class "Default")
      (node (ref "R16") (pin "2") (pinfunction "2_2") (pintype "passive"))
      (node (ref "U2") (pin "1") (pinfunction "VOUT_1") (pintype "output"))
    )
    (net (code "59") (name "PWMA1") (class "Default")
      (node (ref "IC1") (pin "14") (pinfunction "PWM1H1/RTCC/RP14/CN12/PMWR/RB14_14") (pintype "bidirectional"))
      (node (ref "SV1") (pin "9") (pinfunction "9_9") (pintype "passive"))
    )
    (net (code "60") (name "PWMA2") (class "Default")
      (node (ref "IC1") (pin "10") (pinfunction "PWM1H2/DAC1RP/RP12/CN14/PMD0/RB12_10") (pintype "bidirectional"))
      (node (ref "SV1") (pin "10") (pinfunction "10_10") (pintype "passive"))
    )
    (net (code "61") (name "PWMB1") (class "Default")
      (node (ref "IC1") (pin "15") (pinfunction "PWM1L1/RP15/CN11/PMCS1/RB15_15") (pintype "bidirectional"))
      (node (ref "SV1") (pin "11") (pinfunction "11_11") (pintype "passive"))
    )
    (net (code "62") (name "PWMB2") (class "Default")
      (node (ref "IC1") (pin "11") (pinfunction "PWM1L2/DAC1RN/RP13/CN13/PMRD/RB13_11") (pintype "bidirectional"))
      (node (ref "SV1") (pin "12") (pinfunction "12_12") (pintype "passive"))
    )
    (net (code "63") (name "RX1") (class "Default")
      (node (ref "IC1") (pin "38") (pinfunction "RP21/CN26/PMA3/RC5_38") (pintype "bidirectional"))
      (node (ref "SV2") (pin "7") (pinfunction "7_7") (pintype "passive"))
    )
    (net (code "64") (name "RX2") (class "Default")
      (node (ref "IC1") (pin "24") (pinfunction "AN5/C1IN+/RP3/CN7/RB3_24") (pintype "bidirectional"))
      (node (ref "SV2") (pin "11") (pinfunction "11_11") (pintype "passive"))
    )
    (net (code "65") (name "SCL") (class "Default")
      (node (ref "IC1") (pin "44") (pinfunction "SCL1/RP8/CN22/PMD4/RB8_44") (pintype "bidirectional"))
      (node (ref "IC2") (pin "6") (pinfunction "SCL_6") (pintype "input"))
      (node (ref "R3") (pin "2") (pinfunction "2_2") (pintype "passive"))
      (node (ref "SV2") (pin "8") (pinfunction "8_8") (pintype "passive"))
    )
    (net (code "66") (name "SDA") (class "Default")
      (node (ref "IC1") (pin "1") (pinfunction "SDA1/RP9/CN21/PMD3/RB9_1") (pintype "bidirectional"))
      (node (ref "IC2") (pin "5") (pinfunction "SDA_5") (pintype "bidirectional"))
      (node (ref "R7") (pin "2") (pinfunction "2_2") (pintype "passive"))
      (node (ref "SV2") (pin "6") (pinfunction "6_6") (pintype "passive"))
    )
    (net (code "67") (name "TX1") (class "Default")
      (node (ref "IC1") (pin "37") (pinfunction "RP20/CN25/PMA4/RC4_37") (pintype "bidirectional"))
      (node (ref "SV2") (pin "5") (pinfunction "5_5") (pintype "passive"))
    )
    (net (code "68") (name "TX2") (class "Default")
      (node (ref "IC1") (pin "23") (pinfunction "AN4/C1IN-/RP2/CN6/RB2_23") (pintype "bidirectional"))
      (node (ref "SV2") (pin "13") (pinfunction "13_13") (pintype "passive"))
    )
    (net (code "69") (name "VENC") (class "Default")
      (node (ref "J1") (pin "2") (pinfunction "2_2") (pintype "passive"))
      (node (ref "SV1") (pin "3") (pinfunction "3_3") (pintype "passive"))
      (node (ref "SV1") (pin "4") (pinfunction "4_4") (pintype "passive"))
    )
  )
)
